# Microcomputer.net
KiCad netlist of a schematic drawn in Altium Designer
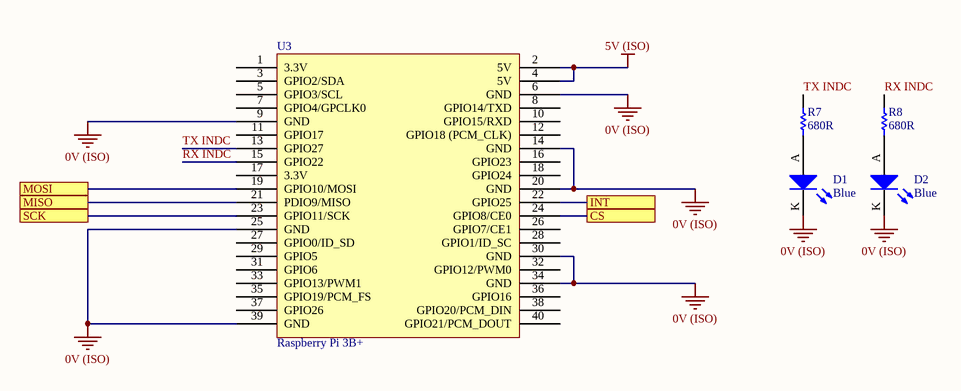
[diagram p0: Microcomputer.SchDoc]

(export (version "E")
  (design (tool "Eeschema 10.0.6"))
  (components
    (comp (ref "D1")
      (value "Blue")
      (footprint "0805 LED")
      (description "LED BLUE CLEAR 2012 SMD")
      (fields
        (field (name "PART NUMBER") "SML-MN2BCTT86C")
        (field (name "MANUFACTURER") "ROHM Semiconductor")
      )
      (libsource (lib "ts_20-standard-library") (part "LED"))
    )
    (comp (ref "D2")
      (value "Blue")
      (footprint "0805 LED")
      (description "LED BLUE CLEAR 2012 SMD")
      (fields
        (field (name "PART NUMBER") "SML-MN2BCTT86C")
        (field (name "MANUFACTURER") "ROHM Semiconductor")
      )
      (libsource (lib "ts_20-standard-library") (part "LED"))
    )
    (comp (ref "R7")
      (value "680R")
      (footprint "0805")
      (fields
        (field (name "PART NUMBER") "RC0805FR07680RL")
        (field (name "MANUFACTURER") "YAGEO")
        (field (name "TOLERANCE") "0.01")
      )
      (libsource (lib "ts_20-standard-library") (part "Resistor"))
    )
    (comp (ref "R8")
      (value "680R")
      (footprint "0805")
      (fields
        (field (name "PART NUMBER") "RC0805FR07680RL")
        (field (name "MANUFACTURER") "YAGEO")
        (field (name "TOLERANCE") "0.01")
      )
      (libsource (lib "ts_20-standard-library") (part "Resistor"))
    )
    (comp (ref "U3")
      (value "Raspberry Pi 3B+")
      (footprint "Raspberry Pi 3B+")
      (libsource (lib "ts_20-standard-library") (part "Raspberry Pi 3B+"))
    )
  )
  (nets
    (net (code "1") (name "/CS") (class "Default")
      (node (ref "U3") (pin "24") (pinfunction "GPIO8/CE0_24") (pintype "power_in"))
    )
    (net (code "2") (name "/INT") (class "Default")
      (node (ref "U3") (pin "22") (pinfunction "GPIO25_22") (pintype "power_in"))
    )
    (net (code "3") (name "/MISO") (class "Default")
      (node (ref "U3") (pin "21") (pinfunction "PDIO9/MISO_21") (pintype "power_in"))
    )
    (net (code "4") (name "/MOSI") (class "Default")
      (node (ref "U3") (pin "19") (pinfunction "GPIO10/MOSI_19") (pintype "power_in"))
    )
    (net (code "5") (name "/RX INDC") (class "Default")
      (node (ref "R8") (pin "2") (pinfunction "2_2") (pintype "passive"))
      (node (ref "U3") (pin "15") (pinfunction "GPIO22_15") (pintype "power_in"))
    )
    (net (code "6") (name "/SCK") (class "Default")
      (node (ref "U3") (pin "23") (pinfunction "GPIO11/SCK_23") (pintype "power_in"))
    )
    (net (code "7") (name "/TX INDC") (class "Default")
      (node (ref "R7") (pin "2") (pinfunction "2_2") (pintype "passive"))
      (node (ref "U3") (pin "13") (pinfunction "GPIO27_13") (pintype "power_in"))
    )
    (net (code "8") (name "0V (ISO)") (class "Default")
      (node (ref "D1") (pin "K") (pinfunction "K_K") (pintype "passive"))
      (node (ref "D2") (pin "K") (pinfunction "K_K") (pintype "passive"))
      (node (ref "U3") (pin "14") (pinfunction "GND_14") (pintype "power_in"))
      (node (ref "U3") (pin "20") (pinfunction "GND_20") (pintype "power_in"))
      (node (ref "U3") (pin "25") (pinfunction "GND_25") (pintype "power_in"))
      (node (ref "U3") (pin "30") (pinfunction "GND_30") (pintype "power_in"))
      (node (ref "U3") (pin "34") (pinfunction "GND_34") (pintype "power_in"))
      (node (ref "U3") (pin "39") (pinfunction "GND_39") (pintype "power_in"))
      (node (ref "U3") (pin "6") (pinfunction "GND_6") (pintype "power_in"))
      (node (ref "U3") (pin "9") (pinfunction "GND_9") (pintype "power_in"))
    )
    (net (code "9") (name "5V (ISO)") (class "Default")
      (node (ref "U3") (pin "2") (pinfunction "5V_2") (pintype "power_in"))
      (node (ref "U3") (pin "4") (pinfunction "5V_4") (pintype "power_in"))
    )
    (net (code "10") (name "Net-(D1-PadA)") (class "Default")
      (node (ref "D1") (pin "A") (pinfunction "A_A") (pintype "passive"))
      (node (ref "R7") (pin "1") (pinfunction "1_1") (pintype "passive"))
    )
    (net (code "11") (name "Net-(D2-PadA)") (class "Default")
      (node (ref "D2") (pin "A") (pinfunction "A_A") (pintype "passive"))
      (node (ref "R8") (pin "1") (pinfunction "1_1") (pintype "passive"))
    )
    (net (code "12") (name "unconnected-(U3-3.3V-Pad1)") (class "Default")
      (node (ref "U3") (pin "1") (pinfunction "3.3V_1") (pintype "power_in"))
    )
    (net (code "13") (name "unconnected-(U3-3.3V-Pad17)") (class "Default")
      (node (ref "U3") (pin "17") (pinfunction "3.3V_17") (pintype "power_in"))
    )
    (net (code "14") (name "unconnected-(U3-GPIO0{slash}ID_SD-Pad27)") (class "Default")
      (node (ref "U3") (pin "27") (pinfunction "GPIO0/ID_SD_27") (pintype "power_in"))
    )
    (net (code "15") (name "unconnected-(U3-GPIO1{slash}ID_SC-Pad28)") (class "Default")
      (node (ref "U3") (pin "28") (pinfunction "GPIO1/ID_SC_28") (pintype "power_in"))
    )
    (net (code "16") (name "unconnected-(U3-GPIO2{slash}SDA-Pad3)") (class "Default")
      (node (ref "U3") (pin "3") (pinfunction "GPIO2/SDA_3") (pintype "power_in"))
    )
    (net (code "17") (name "unconnected-(U3-GPIO3{slash}SCL-Pad5)") (class "Default")
      (node (ref "U3") (pin "5") (pinfunction "GPIO3/SCL_5") (pintype "power_in"))
    )
    (net (code "18") (name "unconnected-(U3-GPIO4{slash}GPCLK0-Pad7)") (class "Default")
      (node (ref "U3") (pin "7") (pinfunction "GPIO4/GPCLK0_7") (pintype "power_in"))
    )
    (net (code "19") (name "unconnected-(U3-GPIO5-Pad29)") (class "Default")
      (node (ref "U3") (pin "29") (pinfunction "GPIO5_29") (pintype "power_in"))
    )
    (net (code "20") (name "unconnected-(U3-GPIO6-Pad31)") (class "Default")
      (node (ref "U3") (pin "31") (pinfunction "GPIO6_31") (pintype "power_in"))
    )
    (net (code "21") (name "unconnected-(U3-GPIO7{slash}CE1-Pad26)") (class "Default")
      (node (ref "U3") (pin "26") (pinfunction "GPIO7/CE1_26") (pintype "power_in"))
    )
    (net (code "22") (name "unconnected-(U3-GPIO12{slash}PWM0-Pad32)") (class "Default")
      (node (ref "U3") (pin "32") (pinfunction "GPIO12/PWM0_32") (pintype "power_in"))
    )
    (net (code "23") (name "unconnected-(U3-GPIO13{slash}PWM1-Pad33)") (class "Default")
      (node (ref "U3") (pin "33") (pinfunction "GPIO13/PWM1_33") (pintype "power_in"))
    )
    (net (code "24") (name "unconnected-(U3-GPIO14{slash}TXD-Pad8)") (class "Default")
      (node (ref "U3") (pin "8") (pinfunction "GPIO14/TXD_8") (pintype "power_in"))
    )
    (net (code "25") (name "unconnected-(U3-GPIO15{slash}RXD-Pad10)") (class "Default")
      (node (ref "U3") (pin "10") (pinfunction "GPIO15/RXD_10") (pintype "power_in"))
    )
    (net (code "26") (name "unconnected-(U3-GPIO16-Pad36)") (class "Default")
      (node (ref "U3") (pin "36") (pinfunction "GPIO16_36") (pintype "power_in"))
    )
    (net (code "27") (name "unconnected-(U3-GPIO17-Pad11)") (class "Default")
      (node (ref "U3") (pin "11") (pinfunction "GPIO17_11") (pintype "power_in"))
    )
    (net (code "28") (name "unconnected-(U3-GPIO18_(PCM_CLK)-Pad12)") (class "Default")
      (node (ref "U3") (pin "12") (pinfunction "GPIO18_(PCM_CLK)_12") (pintype "power_in"))
    )
    (net (code "29") (name "unconnected-(U3-GPIO19{slash}PCM_FS-Pad35)") (class "Default")
      (node (ref "U3") (pin "35") (pinfunction "GPIO19/PCM_FS_35") (pintype "power_in"))
    )
    (net (code "30") (name "unconnected-(U3-GPIO20{slash}PCM_DIN-Pad38)") (class "Default")
      (node (ref "U3") (pin "38") (pinfunction "GPIO20/PCM_DIN_38") (pintype "power_in"))
    )
    (net (code "31") (name "unconnected-(U3-GPIO21{slash}PCM_DOUT-Pad40)") (class "Default")
      (node (ref "U3") (pin "40") (pinfunction "GPIO21/PCM_DOUT_40") (pintype "power_in"))
    )
    (net (code "32") (name "unconnected-(U3-GPIO23-Pad16)") (class "Default")
      (node (ref "U3") (pin "16") (pinfunction "GPIO23_16") (pintype "power_in"))
    )
    (net (code "33") (name "unconnected-(U3-GPIO24-Pad18)") (class "Default")
      (node (ref "U3") (pin "18") (pinfunction "GPIO24_18") (pintype "power_in"))
    )
    (net (code "34") (name "unconnected-(U3-GPIO26-Pad37)") (class "Default")
      (node (ref "U3") (pin "37") (pinfunction "GPIO26_37") (pintype "power_in"))
    )
  )
)
